# Sensor_interfacing.net
KiCad netlist of a schematic drawn in Altium Designer
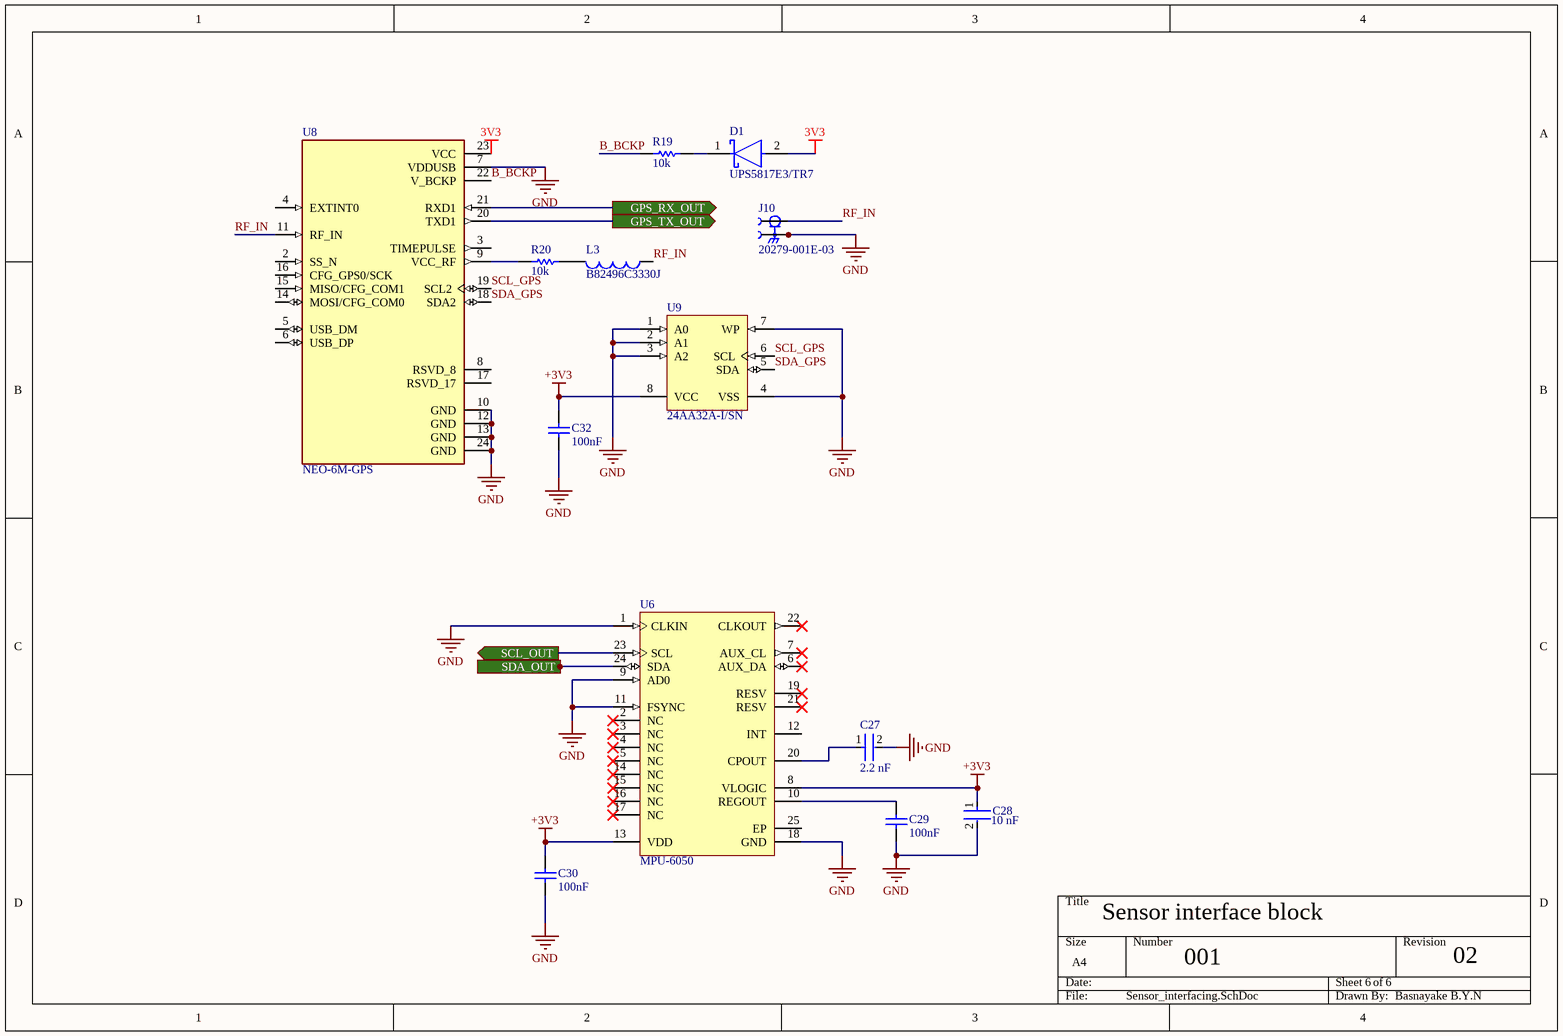
[diagram p0: Sensor_interfacing.SchDoc]

(export (version "E")
  (design (tool "Eeschema 10.0.6"))
  (components
    (comp (ref "C27")
      (value "CC0402KRX7R9BB222")
      (footprint "FP-CC0402-MFG")
      (description "CAP CER 2200PF 50V X7R 0402")
      (fields
        (field (name "TOLERANCE") "0.1")
        (field (name "OCTOPART") "https://octopart.com/cc0402krx7r9bb222-yageo-39467642")
        (field (name "CAPACITANCE") "2.2 nF")
      )
      (libsource (lib "Altium Content Vault") (part "11868f565c42a9108669ba33697ecf6"))
    )
    (comp (ref "C28")
      (value "CC0402KRX7R9BB103")
      (footprint "FP-CC0402-MFG")
      (description "CAP CER 10000PF 50V X7R 0402")
      (fields
        (field (name "OCTOPART") "https://octopart.com/cc0402krx7r9bb103-yageo-8376513")
        (field (name "CAPACITANCE") "10 nF")
        (field (name "MANUFACTURER") "YAGEO")
      )
      (libsource (lib "Altium Content Vault") (part "11868f565c42a9108669ba33697ecf6"))
    )
    (comp (ref "C29")
      (value "CL05B104KO5NNNC")
      (footprint "CAPC1050X55X23ML05T13")
      (description "Chip Capacitor, 100 nF, +/- 10%, 16 V, -55 to 125 degC, 0402 (1005 Metric), RoHS, Tape and Reel")
      (fields (field (name "MANUFACTURER") "Samsung Electro-Mechanics") (field (name "CAPACITANCE") "100nF"))
      (libsource (lib "Altium Content Vault") (part "CAP-NP-2"))
    )
    (comp (ref "C30")
      (value "CL05B104KO5NNNC")
      (footprint "CAPC1050X55X23ML05T13")
      (description "Chip Capacitor, 100 nF, +/- 10%, 16 V, -55 to 125 degC, 0402 (1005 Metric), RoHS, Tape and Reel")
      (fields (field (name "MANUFACTURER") "Samsung Electro-Mechanics") (field (name "CAPACITANCE") "100nF"))
      (libsource (lib "Altium Content Vault") (part "CAP-NP-2"))
    )
    (comp (ref "C32")
      (value "CL05B104KO5NNNC")
      (footprint "CAPC1050X55X23ML05T13")
      (description "Chip Capacitor, 100 nF, +/- 10%, 16 V, -55 to 125 degC, 0402 (1005 Metric), RoHS, Tape and Reel")
      (fields (field (name "MANUFACTURER") "Samsung Electro-Mechanics") (field (name "CAPACITANCE") "100nF"))
      (libsource (lib "Altium Content Vault") (part "CAP-NP-2"))
    )
    (comp (ref "D1")
      (value "UPS5817E3/TR7")
      (footprint "FP-DO-216AA-MFG")
      (description "UPS5817E3/TR7 Rectifier Diode, Schottky, 1 Phase, 1 Element, 1A, 20V V(RRM), Silicon, DO-216AA")
      (libsource (lib "Altium Content Vault") (part "8009945c061e5870b38833d7418a593"))
    )
    (comp (ref "J10")
      (value "20279-001E-03")
      (footprint "IPEX_20279-001E-03")
      (fields (field (name "MF") "I-PEX"))
      (libsource (lib "20279-001E-03") (part "20279-001E-03"))
    )
    (comp (ref "L3")
      (value "B82496C3330J")
      (footprint "INDC1608X90X30LL10T20")
      (fields (field (name "MANUFACTURER") "EPCOS-(TDK)") (field (name "TOLERANCE") "±5%"))
      (libsource (lib "Altium Content Vault") (part "IND-2"))
    )
    (comp (ref "R19")
      (value "RC0805FR-0710KL")
      (footprint "RESC2013X60X35NL10T20")
      (description "Chip Resistor, 10 KOhm, +/- 1%, 0.125 W, -55 to 155 degC, 0805 (2012 Metric), RoHS, Tape and Reel")
      (fields (field (name "MANUFACTURER") "Yageo") (field (name "PARAMETER 1") "10k"))
      (libsource (lib "Altium Content Vault") (part "RES-2"))
    )
    (comp (ref "R20")
      (value "RC0805FR-0710KL")
      (footprint "RESC2013X60X35NL10T20")
      (description "Chip Resistor, 10 KOhm, +/- 1%, 0.125 W, -55 to 155 degC, 0805 (2012 Metric), RoHS, Tape and Reel")
      (fields (field (name "MANUFACTURER") "Yageo") (field (name "PARAMETER 1") "10k"))
      (libsource (lib "Altium Content Vault") (part "RES-2"))
    )
    (comp (ref "U6")
      (value "MPU-6050")
      (footprint "IS-QFN-24_V")
      (fields (field (name "MANUFACTURER") "InvenSense"))
      (libsource (lib "Altium Content Vault") (part "IS-MPU-6050-QFN-24"))
    )
    (comp (ref "U8")
      (value "NEO-6M-GPS")
      (footprint "XCVR_NEO-6M-GPS")
      (description "GPS Development Tools SparkFun GNSS-RTK Dead Reckoning Breakout - ZED-F9K (Qwiic)")
      (fields (field (name "MF") "u-blox"))
      (libsource (lib "EarendelPro_Track") (part "NEO-6M-GPS"))
    )
    (comp (ref "U9")
      (value "24AA32A-I/SN")
      (footprint "SOIC-SN8_L")
      (description "32Kbit, 400kHz, 1.7V, I2C Serial EEPROM, 8-Pin SOIC 150mil, Industrial Temperature")
      (libsource (lib "Altium Content Vault") (part "MEM-SEEPROM-34AA02-IL8"))
    )
  )
  (nets
    (net (code "1") (name "+3V3") (class "Default")
      (node (ref "C28") (pin "1") (pinfunction "1_1") (pintype "passive"))
      (node (ref "C30") (pin "2") (pinfunction "2_2") (pintype "passive"))
      (node (ref "C32") (pin "2") (pinfunction "2_2") (pintype "passive"))
      (node (ref "U6") (pin "13") (pinfunction "VDD_13") (pintype "power_in"))
      (node (ref "U6") (pin "8") (pinfunction "VLOGIC_8") (pintype "power_in"))
      (node (ref "U9") (pin "8") (pinfunction "VCC_8") (pintype "power_in"))
    )
    (net (code "2") (name "/B_BCKP") (class "Default")
      (node (ref "R19") (pin "1") (pinfunction "1_1") (pintype "passive"))
      (node (ref "U8") (pin "22") (pinfunction "V_BCKP_22") (pintype "power_in"))
    )
    (net (code "3") (name "/GPS_RX_OUT") (class "Default")
      (node (ref "U8") (pin "21") (pinfunction "RXD1_21") (pintype "input"))
    )
    (net (code "4") (name "/GPS_TX_OUT") (class "Default")
      (node (ref "U8") (pin "20") (pinfunction "TXD1_20") (pintype "output"))
    )
    (net (code "5") (name "/RF_IN") (class "Default")
      (node (ref "J10") (pin "1") (pinfunction "SIGNAL_1") (pintype "passive"))
      (node (ref "L3") (pin "1") (pinfunction "1_1") (pintype "passive"))
      (node (ref "U8") (pin "11") (pinfunction "RF_IN_11") (pintype "input"))
    )
    (net (code "6") (name "/SCL_GPS") (class "Default")
      (node (ref "U8") (pin "19") (pinfunction "SCL2_19") (pintype "bidirectional"))
      (node (ref "U9") (pin "6") (pinfunction "SCL_6") (pintype "input"))
    )
    (net (code "7") (name "/SCL_OUT") (class "Default")
      (node (ref "U6") (pin "23") (pinfunction "SCL_23") (pintype "input"))
    )
    (net (code "8") (name "/SDA_GPS") (class "Default")
      (node (ref "U8") (pin "18") (pinfunction "SDA2_18") (pintype "bidirectional"))
      (node (ref "U9") (pin "5") (pinfunction "SDA_5") (pintype "bidirectional"))
    )
    (net (code "9") (name "/SDA_OUT") (class "Default")
      (node (ref "U6") (pin "24") (pinfunction "SDA_24") (pintype "bidirectional"))
    )
    (net (code "10") (name "3V3") (class "Default")
      (node (ref "D1") (pin "2") (pinfunction "A_2") (pintype "passive"))
      (node (ref "U8") (pin "23") (pinfunction "VCC_23") (pintype "power_in"))
    )
    (net (code "11") (name "GND") (class "Default")
      (node (ref "C27") (pin "2") (pinfunction "2_2") (pintype "passive"))
      (node (ref "C28") (pin "2") (pinfunction "2_2") (pintype "passive"))
      (node (ref "C29") (pin "1") (pinfunction "1_1") (pintype "passive"))
      (node (ref "C30") (pin "1") (pinfunction "1_1") (pintype "passive"))
      (node (ref "C32") (pin "1") (pinfunction "1_1") (pintype "passive"))
      (node (ref "J10") (pin "2") (pinfunction "GROUND_2") (pintype "passive"))
      (node (ref "J10") (pin "3") (pinfunction "GROUND_3") (pintype "passive"))
      (node (ref "U6") (pin "1") (pinfunction "CLKIN_1") (pintype "input"))
      (node (ref "U6") (pin "11") (pinfunction "FSYNC_11") (pintype "input"))
      (node (ref "U6") (pin "18") (pinfunction "GND_18") (pintype "power_in"))
      (node (ref "U6") (pin "9") (pinfunction "AD0_9") (pintype "input"))
      (node (ref "U8") (pin "10") (pinfunction "GND_10") (pintype "power_in"))
      (node (ref "U8") (pin "12") (pinfunction "GND_12") (pintype "power_in"))
      (node (ref "U8") (pin "13") (pinfunction "GND_13") (pintype "power_in"))
      (node (ref "U8") (pin "24") (pinfunction "GND_24") (pintype "power_in"))
      (node (ref "U8") (pin "7") (pinfunction "VDDUSB_7") (pintype "power_in"))
      (node (ref "U9") (pin "1") (pinfunction "A0_1") (pintype "input"))
      (node (ref "U9") (pin "2") (pinfunction "A1_2") (pintype "input"))
      (node (ref "U9") (pin "3") (pinfunction "A2_3") (pintype "input"))
      (node (ref "U9") (pin "4") (pinfunction "VSS_4") (pintype "power_in"))
      (node (ref "U9") (pin "7") (pinfunction "WP_7") (pintype "input"))
    )
    (net (code "12") (name "Net-(D1-C)") (class "Default")
      (node (ref "D1") (pin "1") (pinfunction "C_1") (pintype "passive"))
      (node (ref "R19") (pin "2") (pinfunction "2_2") (pintype "passive"))
    )
    (net (code "13") (name "Net-(L3-Pad2)") (class "Default")
      (node (ref "L3") (pin "2") (pinfunction "2_2") (pintype "passive"))
      (node (ref "R20") (pin "2") (pinfunction "2_2") (pintype "passive"))
    )
    (net (code "14") (name "Net-(U6-CPOUT)") (class "Default")
      (node (ref "C27") (pin "1") (pinfunction "1_1") (pintype "passive"))
      (node (ref "U6") (pin "20") (pinfunction "CPOUT_20") (pintype "passive"))
    )
    (net (code "15") (name "Net-(U6-REGOUT)") (class "Default")
      (node (ref "C29") (pin "2") (pinfunction "2_2") (pintype "passive"))
      (node (ref "U6") (pin "10") (pinfunction "REGOUT_10") (pintype "passive"))
    )
    (net (code "16") (name "Net-(U8-VCC_RF)") (class "Default")
      (node (ref "R20") (pin "1") (pinfunction "1_1") (pintype "passive"))
      (node (ref "U8") (pin "9") (pinfunction "VCC_RF_9") (pintype "output"))
    )
    (net (code "17") (name "unconnected-(U6-AUX_CL-Pad7)") (class "Default")
      (node (ref "U6") (pin "7") (pinfunction "AUX_CL_7") (pintype "output+no_connect"))
    )
    (net (code "18") (name "unconnected-(U6-AUX_DA-Pad6)") (class "Default")
      (node (ref "U6") (pin "6") (pinfunction "AUX_DA_6") (pintype "bidirectional+no_connect"))
    )
    (net (code "19") (name "unconnected-(U6-CLKOUT-Pad22)") (class "Default")
      (node (ref "U6") (pin "22") (pinfunction "CLKOUT_22") (pintype "output+no_connect"))
    )
    (net (code "20") (name "unconnected-(U6-EP-Pad25)") (class "Default")
      (node (ref "U6") (pin "25") (pinfunction "EP_25") (pintype "power_in"))
    )
    (net (code "21") (name "unconnected-(U6-INT-Pad12)") (class "Default")
      (node (ref "U6") (pin "12") (pinfunction "INT_12") (pintype "open_collector"))
    )
    (net (code "22") (name "unconnected-(U6-NC-Pad2)") (class "Default")
      (node (ref "U6") (pin "2") (pinfunction "NC_2") (pintype "passive+no_connect"))
    )
    (net (code "23") (name "unconnected-(U6-NC-Pad3)") (class "Default")
      (node (ref "U6") (pin "3") (pinfunction "NC_3") (pintype "passive+no_connect"))
    )
    (net (code "24") (name "unconnected-(U6-NC-Pad4)") (class "Default")
      (node (ref "U6") (pin "4") (pinfunction "NC_4") (pintype "passive+no_connect"))
    )
    (net (code "25") (name "unconnected-(U6-NC-Pad5)") (class "Default")
      (node (ref "U6") (pin "5") (pinfunction "NC_5") (pintype "passive+no_connect"))
    )
    (net (code "26") (name "unconnected-(U6-NC-Pad14)") (class "Default")
      (node (ref "U6") (pin "14") (pinfunction "NC_14") (pintype "passive+no_connect"))
    )
    (net (code "27") (name "unconnected-(U6-NC-Pad15)") (class "Default")
      (node (ref "U6") (pin "15") (pinfunction "NC_15") (pintype "passive+no_connect"))
    )
    (net (code "28") (name "unconnected-(U6-NC-Pad16)") (class "Default")
      (node (ref "U6") (pin "16") (pinfunction "NC_16") (pintype "passive+no_connect"))
    )
    (net (code "29") (name "unconnected-(U6-NC-Pad17)") (class "Default")
      (node (ref "U6") (pin "17") (pinfunction "NC_17") (pintype "passive+no_connect"))
    )
    (net (code "30") (name "unconnected-(U6-RESV-Pad19)") (class "Default")
      (node (ref "U6") (pin "19") (pinfunction "RESV_19") (pintype "passive+no_connect"))
    )
    (net (code "31") (name "unconnected-(U6-RESV-Pad21)") (class "Default")
      (node (ref "U6") (pin "21") (pinfunction "RESV_21") (pintype "passive+no_connect"))
    )
    (net (code "32") (name "unconnected-(U8-CFG_GPS0{slash}SCK-Pad16)") (class "Default")
      (node (ref "U8") (pin "16") (pinfunction "CFG_GPS0/SCK_16") (pintype "input"))
    )
    (net (code "33") (name "unconnected-(U8-EXTINT0-Pad4)") (class "Default")
      (node (ref "U8") (pin "4") (pinfunction "EXTINT0_4") (pintype "input"))
    )
    (net (code "34") (name "unconnected-(U8-MISO{slash}CFG_COM1-Pad15)") (class "Default")
      (node (ref "U8") (pin "15") (pinfunction "MISO/CFG_COM1_15") (pintype "input"))
    )
    (net (code "35") (name "unconnected-(U8-MOSI{slash}CFG_COM0-Pad14)") (class "Default")
      (node (ref "U8") (pin "14") (pinfunction "MOSI/CFG_COM0_14") (pintype "bidirectional"))
    )
    (net (code "36") (name "unconnected-(U8-RSVD_8-Pad8)") (class "Default")
      (node (ref "U8") (pin "8") (pinfunction "RSVD_8_8") (pintype "passive"))
    )
    (net (code "37") (name "unconnected-(U8-RSVD_17-Pad17)") (class "Default")
      (node (ref "U8") (pin "17") (pinfunction "RSVD_17_17") (pintype "passive"))
    )
    (net (code "38") (name "unconnected-(U8-SS_N-Pad2)") (class "Default")
      (node (ref "U8") (pin "2") (pinfunction "SS_N_2") (pintype "input"))
    )
    (net (code "39") (name "unconnected-(U8-TIMEPULSE-Pad3)") (class "Default")
      (node (ref "U8") (pin "3") (pinfunction "TIMEPULSE_3") (pintype "output"))
    )
    (net (code "40") (name "unconnected-(U8-USB_DM-Pad5)") (class "Default")
      (node (ref "U8") (pin "5") (pinfunction "USB_DM_5") (pintype "bidirectional"))
    )
    (net (code "41") (name "unconnected-(U8-USB_DP-Pad6)") (class "Default")
      (node (ref "U8") (pin "6") (pinfunction "USB_DP_6") (pintype "bidirectional"))
    )
  )
)
